# MODULIQ_RF_Detector.net
KiCad netlist of a schematic drawn in Altium Designer
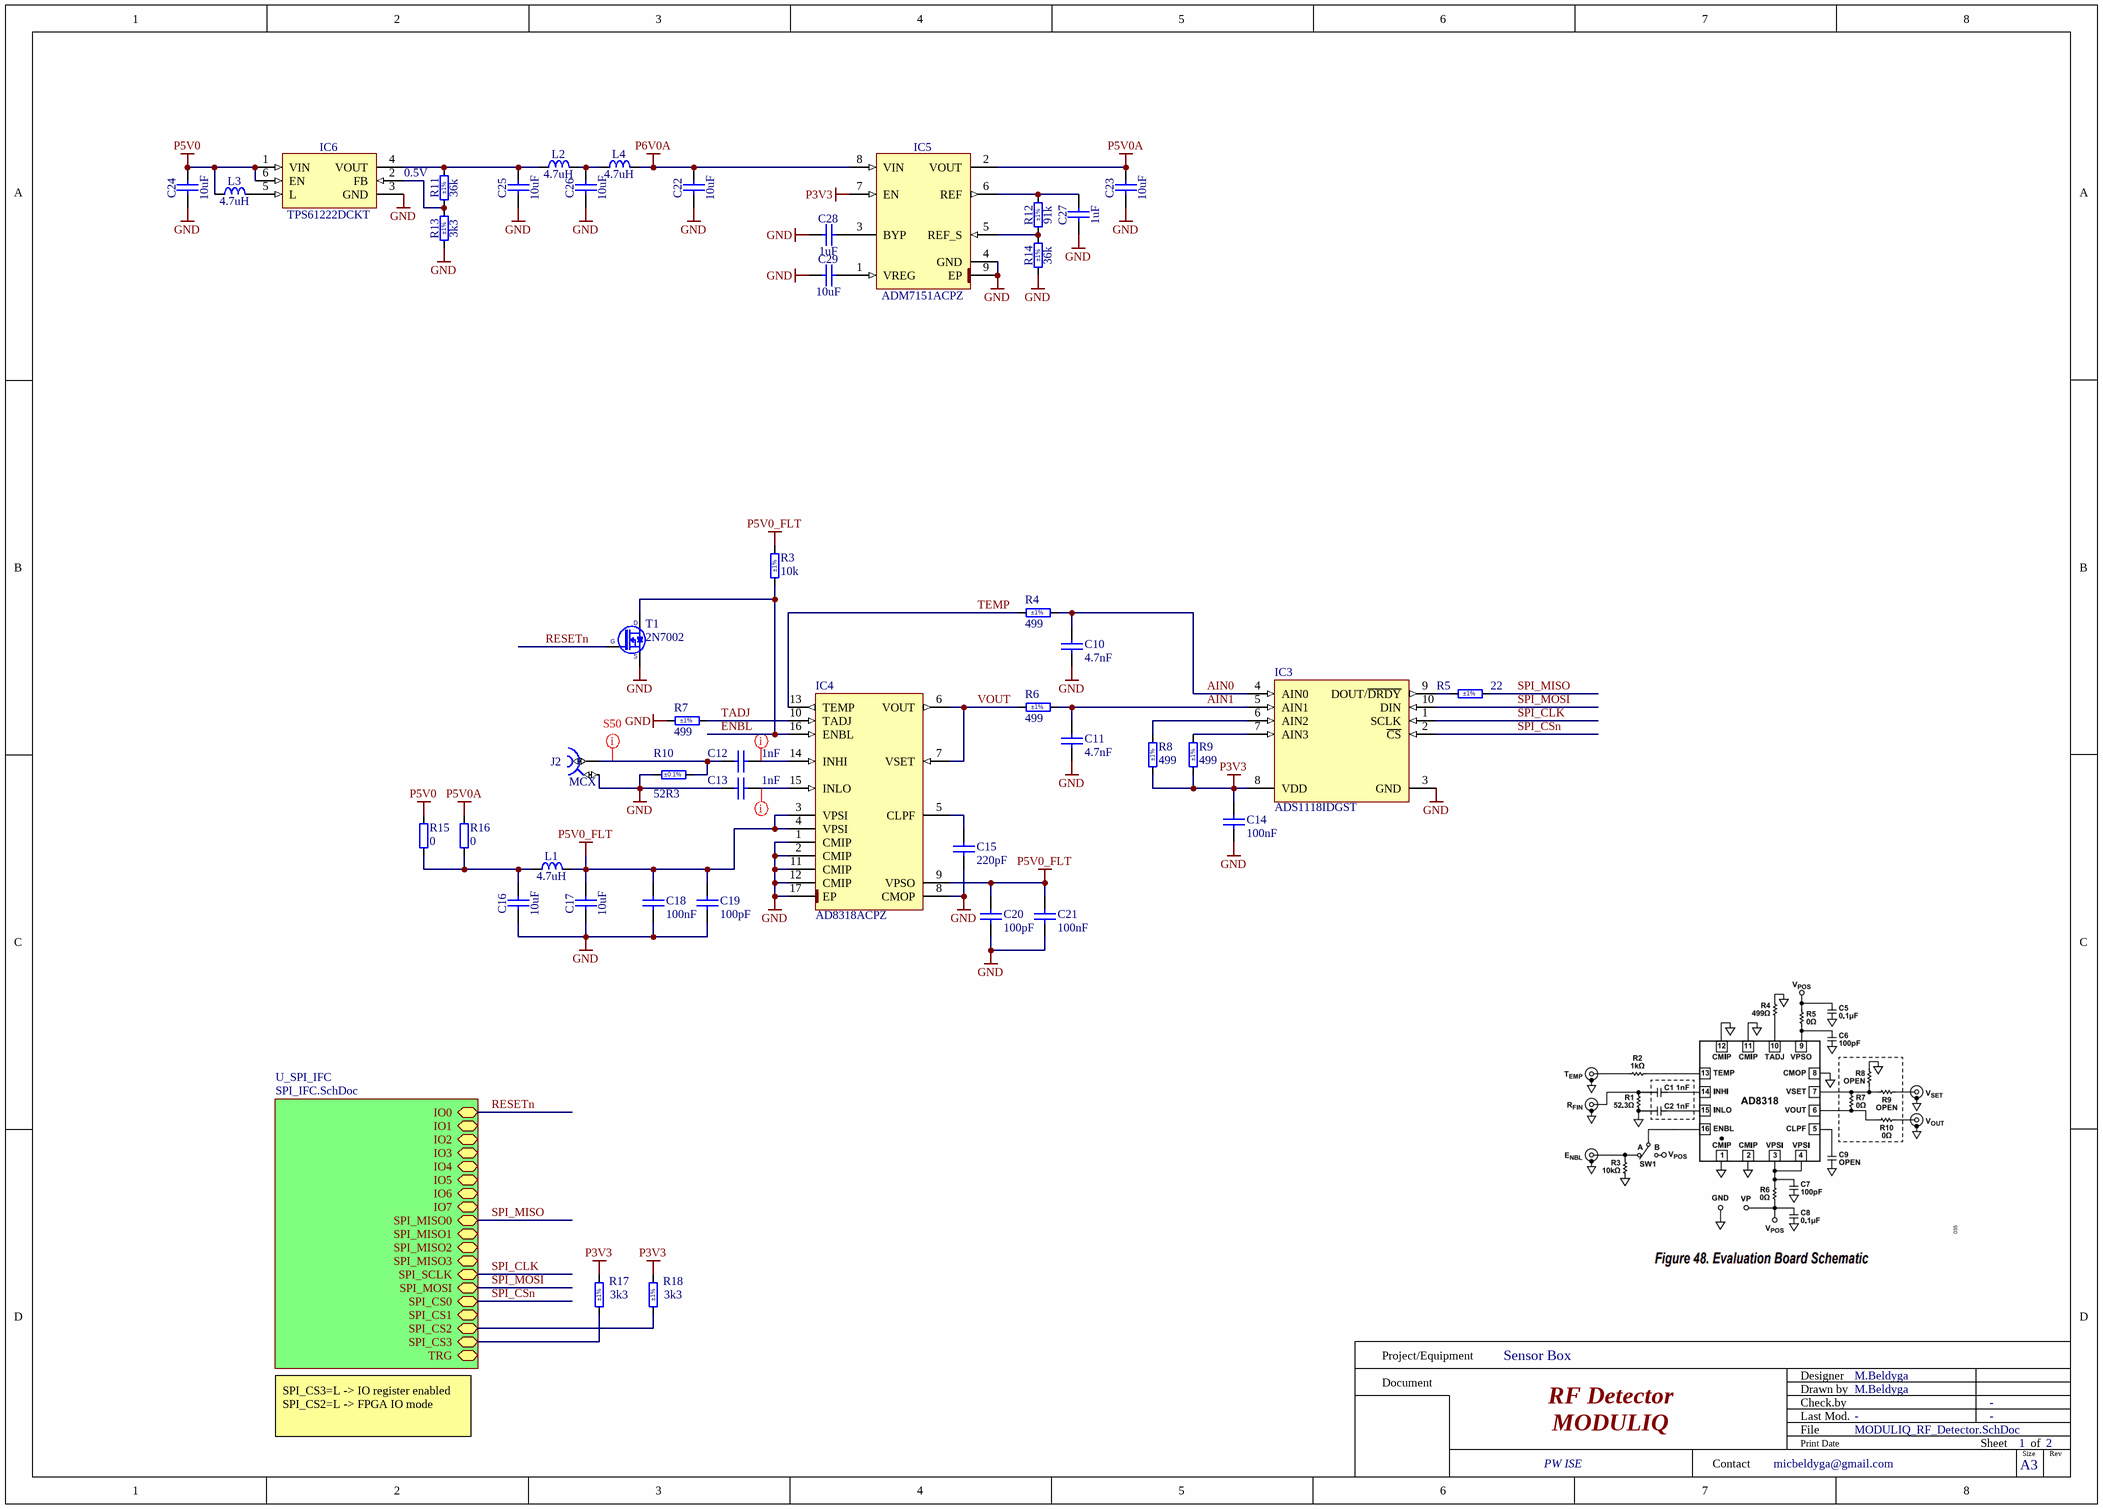
[diagram p0: MODULIQ_RF_Detector.SchDoc]

(export (version "E")
  (design (tool "Eeschema 10.0.6"))
  (components
    (comp (ref "C10")
      (value "4.7nF")
      (footprint "CAPC1005X55N")
      (description "Non-polarised capacitor")
      (fields
        (field (name "PART NUMBER") "CC0402_4.7NF_16V_10%_X7R")
        (field (name "VOLTAGE") "16V")
        (field (name "AUTHOR") "CERN DEM JLC")
      )
      (libsource (lib "Capacitors") (part "Capacitor - non polarized"))
    )
    (comp (ref "C11")
      (value "4.7nF")
      (footprint "CAPC1005X55N")
      (description "Non-polarised capacitor")
      (fields
        (field (name "PART NUMBER") "CC0402_4.7NF_16V_10%_X7R")
        (field (name "VOLTAGE") "16V")
        (field (name "AUTHOR") "CERN DEM JLC")
      )
      (libsource (lib "Capacitors") (part "Capacitor - non polarized"))
    )
    (comp (ref "C12")
      (value "1nF")
      (footprint "CAPC1005X55N")
      (description "Non-polarised capacitor")
      (fields
        (field (name "PART NUMBER") "CC0402_1NF_50V_5%_C0G")
        (field (name "VOLTAGE") "50V")
        (field (name "AUTHOR") "CERN DEM BC")
      )
      (libsource (lib "Capacitors") (part "Capacitor - non polarized"))
    )
    (comp (ref "C13")
      (value "1nF")
      (footprint "CAPC1005X55N")
      (description "Non-polarised capacitor")
      (fields
        (field (name "PART NUMBER") "CC0402_1NF_50V_5%_C0G")
        (field (name "VOLTAGE") "50V")
        (field (name "AUTHOR") "CERN DEM BC")
      )
      (libsource (lib "Capacitors") (part "Capacitor - non polarized"))
    )
    (comp (ref "C14")
      (value "100nF")
      (footprint "CAPC1005X55N")
      (description "Non-polarised capacitor")
      (fields
        (field (name "PART NUMBER") "CC0402_100NF_16V_10%_X7R")
        (field (name "VOLTAGE") "16V")
        (field (name "AUTHOR") "CERN DEM JLC")
      )
      (libsource (lib "Capacitors") (part "Capacitor - non polarized"))
    )
    (comp (ref "C15")
      (value "220pF")
      (footprint "CAPC1005X55N")
      (description "Non-polarised capacitor")
      (fields
        (field (name "PART NUMBER") "CC0402_220PF_50V_1%_C0G")
        (field (name "VOLTAGE") "50V")
        (field (name "AUTHOR") "CERN DEM BC")
      )
      (libsource (lib "Capacitors") (part "Capacitor - non polarized"))
    )
    (comp (ref "C16")
      (value "10uF")
      (footprint "CAPC2012X135N")
      (description "Non-polarised capacitor")
      (fields
        (field (name "PART NUMBER") "CC0805_10UF_16V_10%_X5R")
        (field (name "VOLTAGE") "16V")
        (field (name "AUTHOR") "CERN DEM JLC")
      )
      (libsource (lib "Capacitors") (part "Capacitor - non polarized"))
    )
    (comp (ref "C17")
      (value "10uF")
      (footprint "CAPC2012X135N")
      (description "Non-polarised capacitor")
      (fields
        (field (name "PART NUMBER") "CC0805_10UF_16V_10%_X5R")
        (field (name "VOLTAGE") "16V")
        (field (name "AUTHOR") "CERN DEM JLC")
      )
      (libsource (lib "Capacitors") (part "Capacitor - non polarized"))
    )
    (comp (ref "C18")
      (value "100nF")
      (footprint "CAPC1005X55N")
      (description "Non-polarised capacitor")
      (fields
        (field (name "PART NUMBER") "CC0402_100NF_16V_10%_X7R")
        (field (name "VOLTAGE") "16V")
        (field (name "AUTHOR") "CERN DEM JLC")
      )
      (libsource (lib "Capacitors") (part "Capacitor - non polarized"))
    )
    (comp (ref "C19")
      (value "100pF")
      (footprint "CAPC1005X55N")
      (description "Non-polarised capacitor")
      (fields
        (field (name "PART NUMBER") "CC0402_100PF_25V_1%_C0G")
        (field (name "VOLTAGE") "25V")
        (field (name "AUTHOR") "CERN DEM HF")
      )
      (libsource (lib "Capacitors") (part "Capacitor - non polarized"))
    )
    (comp (ref "C20")
      (value "100pF")
      (footprint "CAPC1005X55N")
      (description "Non-polarised capacitor")
      (fields
        (field (name "PART NUMBER") "CC0402_100PF_25V_1%_C0G")
        (field (name "VOLTAGE") "25V")
        (field (name "AUTHOR") "CERN DEM HF")
      )
      (libsource (lib "Capacitors") (part "Capacitor - non polarized"))
    )
    (comp (ref "C21")
      (value "100nF")
      (footprint "CAPC1005X55N")
      (description "Non-polarised capacitor")
      (fields
        (field (name "PART NUMBER") "CC0402_100NF_16V_10%_X7R")
        (field (name "VOLTAGE") "16V")
        (field (name "AUTHOR") "CERN DEM JLC")
      )
      (libsource (lib "Capacitors") (part "Capacitor - non polarized"))
    )
    (comp (ref "C22")
      (value "10uF")
      (footprint "CAPC1608X80N")
      (description "Non-polarised capacitor")
      (fields
        (field (name "PART NUMBER") "CC0603_10UF_10V_10%_X5R")
        (field (name "VOLTAGE") "10V")
        (field (name "AUTHOR") "CERN DEM JLC")
      )
      (libsource (lib "Capacitors") (part "Capacitor - non polarized"))
    )
    (comp (ref "C23")
      (value "10uF")
      (footprint "CAPC1608X80N")
      (description "Non-polarised capacitor")
      (fields
        (field (name "PART NUMBER") "CC0603_10UF_10V_10%_X5R")
        (field (name "VOLTAGE") "10V")
        (field (name "AUTHOR") "CERN DEM JLC")
      )
      (libsource (lib "Capacitors") (part "Capacitor - non polarized"))
    )
    (comp (ref "C24")
      (value "10uF")
      (footprint "CAPC1608X80N")
      (description "Non-polarised capacitor")
      (fields
        (field (name "PART NUMBER") "CC0603_10UF_10V_10%_X5R")
        (field (name "VOLTAGE") "10V")
        (field (name "AUTHOR") "CERN DEM JLC")
      )
      (libsource (lib "Capacitors") (part "Capacitor - non polarized"))
    )
    (comp (ref "C25")
      (value "10uF")
      (footprint "CAPC1608X80N")
      (description "Non-polarised capacitor")
      (fields
        (field (name "PART NUMBER") "CC0603_10UF_10V_10%_X5R")
        (field (name "VOLTAGE") "10V")
        (field (name "AUTHOR") "CERN DEM JLC")
      )
      (libsource (lib "Capacitors") (part "Capacitor - non polarized"))
    )
    (comp (ref "C26")
      (value "10uF")
      (footprint "CAPC1608X80N")
      (description "Non-polarised capacitor")
      (fields
        (field (name "PART NUMBER") "CC0603_10UF_10V_10%_X5R")
        (field (name "VOLTAGE") "10V")
        (field (name "AUTHOR") "CERN DEM JLC")
      )
      (libsource (lib "Capacitors") (part "Capacitor - non polarized"))
    )
    (comp (ref "C27")
      (value "1uF")
      (footprint "CAPC1005X55N")
      (description "Non-polarised capacitor")
      (fields
        (field (name "PART NUMBER") "CC0402_1UF_16V_10%_X5R")
        (field (name "VOLTAGE") "16V")
        (field (name "AUTHOR") "CERN DEM JLC")
      )
      (libsource (lib "Capacitors") (part "Capacitor - non polarized"))
    )
    (comp (ref "C28")
      (value "1uF")
      (footprint "CAPC1005X55N")
      (description "Non-polarised capacitor")
      (fields
        (field (name "PART NUMBER") "CC0402_1UF_16V_10%_X5R")
        (field (name "VOLTAGE") "16V")
        (field (name "AUTHOR") "CERN DEM JLC")
      )
      (libsource (lib "Capacitors") (part "Capacitor - non polarized"))
    )
    (comp (ref "C29")
      (value "10uF")
      (footprint "CAPC1608X80N")
      (description "Non-polarised capacitor")
      (fields
        (field (name "PART NUMBER") "CC0603_10UF_10V_10%_X5R")
        (field (name "VOLTAGE") "10V")
        (field (name "AUTHOR") "CERN DEM JLC")
      )
      (libsource (lib "Capacitors") (part "Capacitor - non polarized"))
    )
    (comp (ref "IC3")
      (value "ADS1118IDGST")
      (footprint "SOP50P490X110-10N")
      (description "Quad Channel Single ADC Delta-Sigma 860sps 16-bit Serial 10-Pin VSSOP T/R")
      (fields (field (name "MANUFACTURER") "Texas Instruments"))
      (libsource (lib "mb") (part "ADS1118IDGST"))
    )
    (comp (ref "IC4")
      (value "AD8318ACPZ")
      (footprint "QFN65P400X400X100-17N-S225")
      (description "1MHz to 8GHz, 70 dB Logarithmic Detector/Controller")
      (fields
        (field (name "MANUFACTURER") "ANALOG DEVICES")
        (field (name "MANUFACTURER PART NUMBER") "AD8318ACP")
        (field (name "AUTHOR") "CERN DEM JLC")
      )
      (libsource (lib "ICs And Semiconductors") (part "AD8318"))
    )
    (comp (ref "IC5")
      (value "ADM7151ACPZ")
      (footprint "SON50P300X300X80-9N-R170X244")
      (description "800 mA Ultralow Noise, High PSRR, RF Linear Regulator")
      (fields
        (field (name "MANUFACTURER") "ANALOG DEVICES")
        (field (name "MANUFACTURER PART NUMBER") "ADM7151ACP")
        (field (name "AUTHOR") "CERN DEM JLC")
      )
      (libsource (lib "ICs And Semiconductors") (part "ADM7151"))
    )
    (comp (ref "IC6")
      (value "TPS61222DCKT")
      (footprint "SOT65P210X110-6N")
      (description "Low Input Voltage, 0.7V Boost Converter With 5.5uA Quiescent Current")
      (fields
        (field (name "MANUFACTURER") "TEXAS INSTRUMENTS")
        (field (name "MANUFACTURER PART NUMBER") "TPS61222DCK")
        (field (name "AUTHOR") "CERN DEM BC")
      )
      (libsource (lib "ICs And Semiconductors") (part "TPS61222"))
    )
    (comp (ref "J2")
      (value "MCX")
      (footprint "AMPHENOL_919-109J-51PX")
      (fields
        (field (name "PART NUMBER") "AMPHENOL_919-109J-51PX")
        (field (name "MANUFACTURER") "AMPHENOL")
        (field (name "MANUFACTURER PART NUMBER") "919-109J-51PX (MCX6251B1-3GT30G-50)")
        (field (name "AUTHOR") "CERN DEM BC")
      )
      (libsource (lib "Connectors") (part "Coax_1Female_1Shield"))
    )
    (comp (ref "L1")
      (value "4.7uH")
      (footprint "INDC2520X120N")
      (description "Inductor")
      (fields
        (field (name "PART NUMBER") "IND1008_4.7UH_20%_MURATA_DFE252012P")
        (field (name "POWER") "2A")
        (field (name "AUTHOR") "CERN DEM BC")
      )
      (libsource (lib "Inductors & Transformers") (part "Inductor"))
    )
    (comp (ref "L2")
      (value "4.7uH")
      (footprint "INDC2520X120N")
      (description "Inductor")
      (fields
        (field (name "PART NUMBER") "IND1008_4.7UH_20%_MURATA_DFE252012P")
        (field (name "POWER") "2A")
        (field (name "AUTHOR") "CERN DEM BC")
      )
      (libsource (lib "Inductors & Transformers") (part "Inductor"))
    )
    (comp (ref "L3")
      (value "4.7uH")
      (footprint "INDC2520X120N")
      (description "Inductor")
      (fields
        (field (name "PART NUMBER") "IND1008_4.7UH_20%_MURATA_DFE252012P")
        (field (name "POWER") "2A")
        (field (name "AUTHOR") "CERN DEM BC")
      )
      (libsource (lib "Inductors & Transformers") (part "Inductor"))
    )
    (comp (ref "L4")
      (value "4.7uH")
      (footprint "INDC2520X120N")
      (description "Inductor")
      (fields
        (field (name "PART NUMBER") "IND1008_4.7UH_20%_MURATA_DFE252012P")
        (field (name "POWER") "2A")
        (field (name "AUTHOR") "CERN DEM BC")
      )
      (libsource (lib "Inductors & Transformers") (part "Inductor"))
    )
    (comp (ref "R3")
      (value "10k")
      (footprint "RESC1005X40N")
      (description "Resistor - 1%")
      (fields
        (field (name "TOLERANCE") "±1%")
        (field (name "PART NUMBER") "R0402_10K_1%_0.0625W_100PPM")
        (field (name "POWER") "0.0625W")
        (field (name "AUTHOR") "CERN DEM JLC")
      )
      (libsource (lib "Resistors") (part "Resistor - 1%"))
    )
    (comp (ref "R4")
      (value "499")
      (footprint "RESC1005X40N")
      (description "Resistor - 1%")
      (fields
        (field (name "TOLERANCE") "±1%")
        (field (name "PART NUMBER") "R0402_499R_1%_0.1W_100PPM")
        (field (name "POWER") "0.1W")
        (field (name "AUTHOR") "CERN DEM MR")
      )
      (libsource (lib "Resistors") (part "Resistor - 1%"))
    )
    (comp (ref "R5")
      (value "22")
      (footprint "RESC1005X40N")
      (description "Resistor - 1%")
      (fields
        (field (name "TOLERANCE") "±1%")
        (field (name "PART NUMBER") "R0402_22R_1%_0.0625W_100PPM")
        (field (name "POWER") "0.0625W")
        (field (name "AUTHOR") "CERN DEM JLC")
      )
      (libsource (lib "Resistors") (part "Resistor - 1%"))
    )
    (comp (ref "R6")
      (value "499")
      (footprint "RESC1005X40N")
      (description "Resistor - 1%")
      (fields
        (field (name "TOLERANCE") "±1%")
        (field (name "PART NUMBER") "R0402_499R_1%_0.1W_100PPM")
        (field (name "POWER") "0.1W")
        (field (name "AUTHOR") "CERN DEM MR")
      )
      (libsource (lib "Resistors") (part "Resistor - 1%"))
    )
    (comp (ref "R7")
      (value "499")
      (footprint "RESC1005X40N")
      (description "Resistor - 1%")
      (fields
        (field (name "TOLERANCE") "±1%")
        (field (name "PART NUMBER") "R0402_499R_1%_0.1W_100PPM")
        (field (name "POWER") "0.1W")
        (field (name "AUTHOR") "CERN DEM MR")
      )
      (libsource (lib "Resistors") (part "Resistor - 1%"))
    )
    (comp (ref "R8")
      (value "499")
      (footprint "RESC1005X40N")
      (description "Resistor - 1%")
      (fields
        (field (name "TOLERANCE") "±1%")
        (field (name "PART NUMBER") "R0402_499R_1%_0.1W_100PPM")
        (field (name "POWER") "0.1W")
        (field (name "AUTHOR") "CERN DEM MR")
      )
      (libsource (lib "Resistors") (part "Resistor - 1%"))
    )
    (comp (ref "R9")
      (value "499")
      (footprint "RESC1005X40N")
      (description "Resistor - 1%")
      (fields
        (field (name "TOLERANCE") "±1%")
        (field (name "PART NUMBER") "R0402_499R_1%_0.1W_100PPM")
        (field (name "POWER") "0.1W")
        (field (name "AUTHOR") "CERN DEM MR")
      )
      (libsource (lib "Resistors") (part "Resistor - 1%"))
    )
    (comp (ref "R10")
      (value "52R3")
      (footprint "RESC1608X55N")
      (description "Resistor - 0.1%")
      (fields
        (field (name "TOLERANCE") "±0.1%")
        (field (name "PART NUMBER") "R0603_52R3_0.1%_0.063W_10PPM")
        (field (name "POWER") "0.063W")
        (field (name "AUTHOR") "CERN DEM JLC")
      )
      (libsource (lib "Resistors") (part "Resistor - 0.1%"))
    )
    (comp (ref "R11")
      (value "36k")
      (footprint "RESC1005X40N")
      (description "Resistor - 1%")
      (fields
        (field (name "TOLERANCE") "±1%")
        (field (name "PART NUMBER") "R0402_36K_1%_0.0625W_100PPM")
        (field (name "POWER") "0.0625W")
        (field (name "AUTHOR") "CERN DEM JLC")
      )
      (libsource (lib "Resistors") (part "Resistor - 1%"))
    )
    (comp (ref "R12")
      (value "91k")
      (footprint "RESC1005X40N")
      (description "Resistor - 1%")
      (fields
        (field (name "TOLERANCE") "±1%")
        (field (name "PART NUMBER") "R0402_91K_1%_0.0625W_100PPM")
        (field (name "POWER") "0.0625W")
        (field (name "AUTHOR") "CERN DEM JLC")
      )
      (libsource (lib "Resistors") (part "Resistor - 1%"))
    )
    (comp (ref "R13")
      (value "3k3")
      (footprint "RESC1005X40N")
      (description "Resistor - 1%")
      (fields
        (field (name "TOLERANCE") "±1%")
        (field (name "PART NUMBER") "R0402_3K3_1%_0.0625W_100PPM")
        (field (name "POWER") "0.0625W")
        (field (name "AUTHOR") "CERN DEM JLC")
      )
      (libsource (lib "Resistors") (part "Resistor - 1%"))
    )
    (comp (ref "R14")
      (value "36k")
      (footprint "RESC1005X40N")
      (description "Resistor - 1%")
      (fields
        (field (name "TOLERANCE") "±1%")
        (field (name "PART NUMBER") "R0402_36K_1%_0.0625W_100PPM")
        (field (name "POWER") "0.0625W")
        (field (name "AUTHOR") "CERN DEM JLC")
      )
      (libsource (lib "Resistors") (part "Resistor - 1%"))
    )
    (comp (ref "R15")
      (value "0")
      (footprint "RESC1005X40N")
      (description "Resistor")
      (fields
        (field (name "PART NUMBER") "R0402_0R_JUMPER")
        (field (name "MANUFACTURER") "GENERIC")
        (field (name "AUTHOR") "CERN DEM JLC")
      )
      (libsource (lib "Resistors") (part "Resistor"))
    )
    (comp (ref "R16")
      (value "0")
      (footprint "RESC1005X40N")
      (description "Resistor")
      (fields
        (field (name "PART NUMBER") "R0402_0R_JUMPER")
        (field (name "MANUFACTURER") "GENERIC")
        (field (name "AUTHOR") "CERN DEM JLC")
      )
      (libsource (lib "Resistors") (part "Resistor"))
    )
    (comp (ref "R17")
      (value "3k3")
      (footprint "RESC1005X40N")
      (description "Resistor - 1%")
      (fields
        (field (name "TOLERANCE") "±1%")
        (field (name "PART NUMBER") "R0402_3K3_1%_0.0625W_100PPM")
        (field (name "POWER") "0.0625W")
        (field (name "AUTHOR") "CERN DEM JLC")
      )
      (libsource (lib "Resistors") (part "Resistor - 1%"))
    )
    (comp (ref "R18")
      (value "3k3")
      (footprint "RESC1005X40N")
      (description "Resistor - 1%")
      (fields
        (field (name "TOLERANCE") "±1%")
        (field (name "PART NUMBER") "R0402_3K3_1%_0.0625W_100PPM")
        (field (name "POWER") "0.0625W")
        (field (name "AUTHOR") "CERN DEM JLC")
      )
      (libsource (lib "Resistors") (part "Resistor - 1%"))
    )
    (comp (ref "T1")
      (value "2N7002")
      (footprint "SOT95P240X130-3N")
      (description "N-CHANNEL MOSFET WITH DIODE")
      (fields (field (name "MANUFACTURER") "FAIRCHILD SEMICONDUCTOR") (field (name "AUTHOR") "CERN DEM JLC"))
      (libsource (lib "ICs And Semiconductors") (part "N-MOSFET-D 1G 2S 3D"))
    )
  )
  (nets
    (net (code "1") (name "/AIN0") (class "Default")
      (node (ref "C10") (pin "2") (pinfunction "2_2") (pintype "passive"))
      (node (ref "IC3") (pin "4") (pinfunction "AIN0_4") (pintype "input"))
      (node (ref "R4") (pin "2") (pinfunction "2_2") (pintype "passive"))
    )
    (net (code "2") (name "/AIN1") (class "Default")
      (node (ref "C11") (pin "2") (pinfunction "2_2") (pintype "passive"))
      (node (ref "IC3") (pin "5") (pinfunction "AIN1_5") (pintype "input"))
      (node (ref "R6") (pin "2") (pinfunction "2_2") (pintype "passive"))
    )
    (net (code "3") (name "/ENBL") (class "Default")
      (node (ref "IC4") (pin "16") (pinfunction "ENBL_16") (pintype "input"))
      (node (ref "R3") (pin "1") (pinfunction "1_1") (pintype "passive"))
      (node (ref "T1") (pin "3") (pinfunction "D_3") (pintype "passive"))
    )
    (net (code "11") (name "/RESETn") (class "Default")
      (node (ref "T1") (pin "1") (pinfunction "G_1") (pintype "passive"))
    )
    (net (code "12") (name "/SPI_CLK") (class "Default")
      (node (ref "IC3") (pin "1") (pinfunction "SCLK_1") (pintype "input"))
    )
    (net (code "14") (name "/SPI_CS2") (class "Default")
      (node (ref "R18") (pin "2") (pinfunction "2_2") (pintype "passive"))
    )
    (net (code "15") (name "/SPI_CS3") (class "Default")
      (node (ref "R17") (pin "2") (pinfunction "2_2") (pintype "passive"))
    )
    (net (code "16") (name "/SPI_CSn") (class "Default")
      (node (ref "IC3") (pin "2") (pinfunction "~{CS}_2") (pintype "input"))
    )
    (net (code "17") (name "/SPI_MISO") (class "Default")
      (node (ref "R5") (pin "2") (pinfunction "2_2") (pintype "passive"))
    )
    (net (code "21") (name "/SPI_MOSI") (class "Default")
      (node (ref "IC3") (pin "10") (pinfunction "DIN_10") (pintype "input"))
    )
    (net (code "22") (name "/TADJ") (class "Default")
      (node (ref "IC4") (pin "10") (pinfunction "TADJ_10") (pintype "input"))
      (node (ref "R7") (pin "2") (pinfunction "2_2") (pintype "passive"))
    )
    (net (code "23") (name "/TEMP") (class "Default")
      (node (ref "IC4") (pin "13") (pinfunction "TEMP_13") (pintype "output"))
      (node (ref "R4") (pin "1") (pinfunction "1_1") (pintype "passive"))
    )
    (net (code "25") (name "/VOUT") (class "Default")
      (node (ref "IC4") (pin "6") (pinfunction "VOUT_6") (pintype "output"))
      (node (ref "IC4") (pin "7") (pinfunction "VSET_7") (pintype "input"))
      (node (ref "R6") (pin "1") (pinfunction "1_1") (pintype "passive"))
    )
    (net (code "26") (name "GND") (class "Default")
      (node (ref "C10") (pin "1") (pinfunction "1_1") (pintype "passive"))
      (node (ref "C11") (pin "1") (pinfunction "1_1") (pintype "passive"))
      (node (ref "C13") (pin "1") (pinfunction "1_1") (pintype "passive"))
      (node (ref "C14") (pin "1") (pinfunction "1_1") (pintype "passive"))
      (node (ref "C15") (pin "1") (pinfunction "1_1") (pintype "passive"))
      (node (ref "C16") (pin "1") (pinfunction "1_1") (pintype "passive"))
      (node (ref "C17") (pin "1") (pinfunction "1_1") (pintype "passive"))
      (node (ref "C18") (pin "1") (pinfunction "1_1") (pintype "passive"))
      (node (ref "C19") (pin "1") (pinfunction "1_1") (pintype "passive"))
      (node (ref "C20") (pin "1") (pinfunction "1_1") (pintype "passive"))
      (node (ref "C21") (pin "1") (pinfunction "1_1") (pintype "passive"))
      (node (ref "C22") (pin "1") (pinfunction "1_1") (pintype "passive"))
      (node (ref "C23") (pin "1") (pinfunction "1_1") (pintype "passive"))
      (node (ref "C24") (pin "1") (pinfunction "1_1") (pintype "passive"))
      (node (ref "C25") (pin "1") (pinfunction "1_1") (pintype "passive"))
      (node (ref "C26") (pin "1") (pinfunction "1_1") (pintype "passive"))
      (node (ref "C27") (pin "1") (pinfunction "1_1") (pintype "passive"))
      (node (ref "C28") (pin "1") (pinfunction "1_1") (pintype "passive"))
      (node (ref "C29") (pin "1") (pinfunction "1_1") (pintype "passive"))
      (node (ref "IC3") (pin "3") (pinfunction "GND_3") (pintype "power_in"))
      (node (ref "IC4") (pin "1") (pinfunction "CMIP_1") (pintype "power_in"))
      (node (ref "IC4") (pin "11") (pinfunction "CMIP_11") (pintype "power_in"))
      (node (ref "IC4") (pin "12") (pinfunction "CMIP_12") (pintype "power_in"))
      (node (ref "IC4") (pin "17") (pinfunction "EP_17") (pintype "power_in"))
      (node (ref "IC4") (pin "2") (pinfunction "CMIP_2") (pintype "power_in"))
      (node (ref "IC4") (pin "8") (pinfunction "CMOP_8") (pintype "power_in"))
      (node (ref "IC5") (pin "4") (pinfunction "GND_4") (pintype "power_in"))
      (node (ref "IC5") (pin "9") (pinfunction "EP_9") (pintype "power_in"))
      (node (ref "IC6") (pin "3") (pinfunction "GND_3") (pintype "power_in"))
      (node (ref "J2") (pin "2") (pinfunction "2_2") (pintype "bidirectional"))
      (node (ref "R10") (pin "1") (pinfunction "1_1") (pintype "passive"))
      (node (ref "R13") (pin "1") (pinfunction "1_1") (pintype "passive"))
      (node (ref "R14") (pin "1") (pinfunction "1_1") (pintype "passive"))
      (node (ref "R7") (pin "1") (pinfunction "1_1") (pintype "passive"))
      (node (ref "T1") (pin "2") (pinfunction "S_2") (pintype "passive"))
    )
    (net (code "27") (name "Net-(C12-Pad1)") (class "Default")
      (node (ref "C12") (pin "1") (pinfunction "1_1") (pintype "passive"))
      (node (ref "J2") (pin "1") (pinfunction "1_1") (pintype "bidirectional"))
      (node (ref "R10") (pin "2") (pinfunction "2_2") (pintype "passive"))
    )
    (net (code "28") (name "Net-(C16-Pad2)") (class "Default")
      (node (ref "C16") (pin "2") (pinfunction "2_2") (pintype "passive"))
      (node (ref "L1") (pin "1") (pinfunction "1_1") (pintype "passive"))
      (node (ref "R15") (pin "1") (pinfunction "1_1") (pintype "passive"))
      (node (ref "R16") (pin "1") (pinfunction "1_1") (pintype "passive"))
    )
    (net (code "29") (name "Net-(C26-Pad2)") (class "Default")
      (node (ref "C26") (pin "2") (pinfunction "2_2") (pintype "passive"))
      (node (ref "L2") (pin "2") (pinfunction "2_2") (pintype "passive"))
      (node (ref "L4") (pin "1") (pinfunction "1_1") (pintype "passive"))
    )
    (net (code "30") (name "Net-(IC3-AIN2)") (class "Default")
      (node (ref "IC3") (pin "6") (pinfunction "AIN2_6") (pintype "input"))
      (node (ref "R8") (pin "2") (pinfunction "2_2") (pintype "passive"))
    )
    (net (code "31") (name "Net-(IC3-AIN3)") (class "Default")
      (node (ref "IC3") (pin "7") (pinfunction "AIN3_7") (pintype "input"))
      (node (ref "R9") (pin "2") (pinfunction "2_2") (pintype "passive"))
    )
    (net (code "32") (name "Net-(IC3-DOUT{slash}~{DRDY})") (class "Default")
      (node (ref "IC3") (pin "9") (pinfunction "DOUT/~{DRDY}_9") (pintype "output"))
      (node (ref "R5") (pin "1") (pinfunction "1_1") (pintype "passive"))
    )
    (net (code "33") (name "Net-(IC4-CLPF)") (class "Default")
      (node (ref "C15") (pin "2") (pinfunction "2_2") (pintype "passive"))
      (node (ref "IC4") (pin "5") (pinfunction "CLPF_5") (pintype "passive"))
    )
    (net (code "34") (name "Net-(IC4-INHI)") (class "Default")
      (node (ref "C12") (pin "2") (pinfunction "2_2") (pintype "passive"))
      (node (ref "IC4") (pin "14") (pinfunction "INHI_14") (pintype "input"))
    )
    (net (code "35") (name "Net-(IC4-INLO)") (class "Default")
      (node (ref "C13") (pin "2") (pinfunction "2_2") (pintype "passive"))
      (node (ref "IC4") (pin "15") (pinfunction "INLO_15") (pintype "input"))
    )
    (net (code "36") (name "Net-(IC5-BYP)") (class "Default")
      (node (ref "C28") (pin "2") (pinfunction "2_2") (pintype "passive"))
      (node (ref "IC5") (pin "3") (pinfunction "BYP_3") (pintype "passive"))
    )
    (net (code "37") (name "Net-(IC5-REF)") (class "Default")
      (node (ref "C27") (pin "2") (pinfunction "2_2") (pintype "passive"))
      (node (ref "IC5") (pin "6") (pinfunction "REF_6") (pintype "output"))
      (node (ref "R12") (pin "2") (pinfunction "2_2") (pintype "passive"))
    )
    (net (code "38") (name "Net-(IC5-REF_S)") (class "Default")
      (node (ref "IC5") (pin "5") (pinfunction "REF_S_5") (pintype "input"))
      (node (ref "R12") (pin "1") (pinfunction "1_1") (pintype "passive"))
      (node (ref "R14") (pin "2") (pinfunction "2_2") (pintype "passive"))
    )
    (net (code "39") (name "Net-(IC5-VREG)") (class "Default")
      (node (ref "C29") (pin "2") (pinfunction "2_2") (pintype "passive"))
      (node (ref "IC5") (pin "1") (pinfunction "VREG_1") (pintype "input"))
    )
    (net (code "40") (name "Net-(IC6-FB)") (class "Default")
      (node (ref "IC6") (pin "2") (pinfunction "FB_2") (pintype "input"))
      (node (ref "R11") (pin "1") (pinfunction "1_1") (pintype "passive"))
      (node (ref "R13") (pin "2") (pinfunction "2_2") (pintype "passive"))
    )
    (net (code "41") (name "Net-(IC6-L)") (class "Default")
      (node (ref "IC6") (pin "5") (pinfunction "L_5") (pintype "input"))
      (node (ref "L3") (pin "2") (pinfunction "2_2") (pintype "passive"))
    )
    (net (code "42") (name "Net-(IC6-VOUT)") (class "Default")
      (node (ref "C25") (pin "2") (pinfunction "2_2") (pintype "passive"))
      (node (ref "IC6") (pin "4") (pinfunction "VOUT_4") (pintype "power_in"))
      (node (ref "L2") (pin "1") (pinfunction "1_1") (pintype "passive"))
      (node (ref "R11") (pin "2") (pinfunction "2_2") (pintype "passive"))
    )
    (net (code "43") (name "P3V3") (class "Default")
      (node (ref "C14") (pin "2") (pinfunction "2_2") (pintype "passive"))
      (node (ref "IC3") (pin "8") (pinfunction "VDD_8") (pintype "power_in"))
      (node (ref "IC5") (pin "7") (pinfunction "EN_7") (pintype "input"))
      (node (ref "R17") (pin "1") (pinfunction "1_1") (pintype "passive"))
      (node (ref "R18") (pin "1") (pinfunction "1_1") (pintype "passive"))
      (node (ref "R8") (pin "1") (pinfunction "1_1") (pintype "passive"))
      (node (ref "R9") (pin "1") (pinfunction "1_1") (pintype "passive"))
    )
    (net (code "44") (name "P5V0") (class "Default")
      (node (ref "C24") (pin "2") (pinfunction "2_2") (pintype "passive"))
      (node (ref "IC6") (pin "1") (pinfunction "VIN_1") (pintype "input"))
      (node (ref "IC6") (pin "6") (pinfunction "EN_6") (pintype "input"))
      (node (ref "L3") (pin "1") (pinfunction "1_1") (pintype "passive"))
      (node (ref "R15") (pin "2") (pinfunction "2_2") (pintype "passive"))
    )
    (net (code "45") (name "P5V0A") (class "Default")
      (node (ref "C23") (pin "2") (pinfunction "2_2") (pintype "passive"))
      (node (ref "IC5") (pin "2") (pinfunction "VOUT_2") (pintype "power_in"))
      (node (ref "R16") (pin "2") (pinfunction "2_2") (pintype "passive"))
    )
    (net (code "46") (name "P5V0_FLT") (class "Default")
      (node (ref "C17") (pin "2") (pinfunction "2_2") (pintype "passive"))
      (node (ref "C18") (pin "2") (pinfunction "2_2") (pintype "passive"))
      (node (ref "C19") (pin "2") (pinfunction "2_2") (pintype "passive"))
      (node (ref "C20") (pin "2") (pinfunction "2_2") (pintype "passive"))
      (node (ref "C21") (pin "2") (pinfunction "2_2") (pintype "passive"))
      (node (ref "IC4") (pin "3") (pinfunction "VPSI_3") (pintype "power_in"))
      (node (ref "IC4") (pin "4") (pinfunction "VPSI_4") (pintype "power_in"))
      (node (ref "IC4") (pin "9") (pinfunction "VPSO_9") (pintype "power_in"))
      (node (ref "L1") (pin "2") (pinfunction "2_2") (pintype "passive"))
      (node (ref "R3") (pin "2") (pinfunction "2_2") (pintype "passive"))
    )
    (net (code "47") (name "P6V0A") (class "Default")
      (node (ref "C22") (pin "2") (pinfunction "2_2") (pintype "passive"))
      (node (ref "IC5") (pin "8") (pinfunction "VIN_8") (pintype "input"))
      (node (ref "L4") (pin "2") (pinfunction "2_2") (pintype "passive"))
    )
  )
)
